# nixie_brain_main_rev7_1.net
KiCad netlist of a schematic drawn in EAGLE
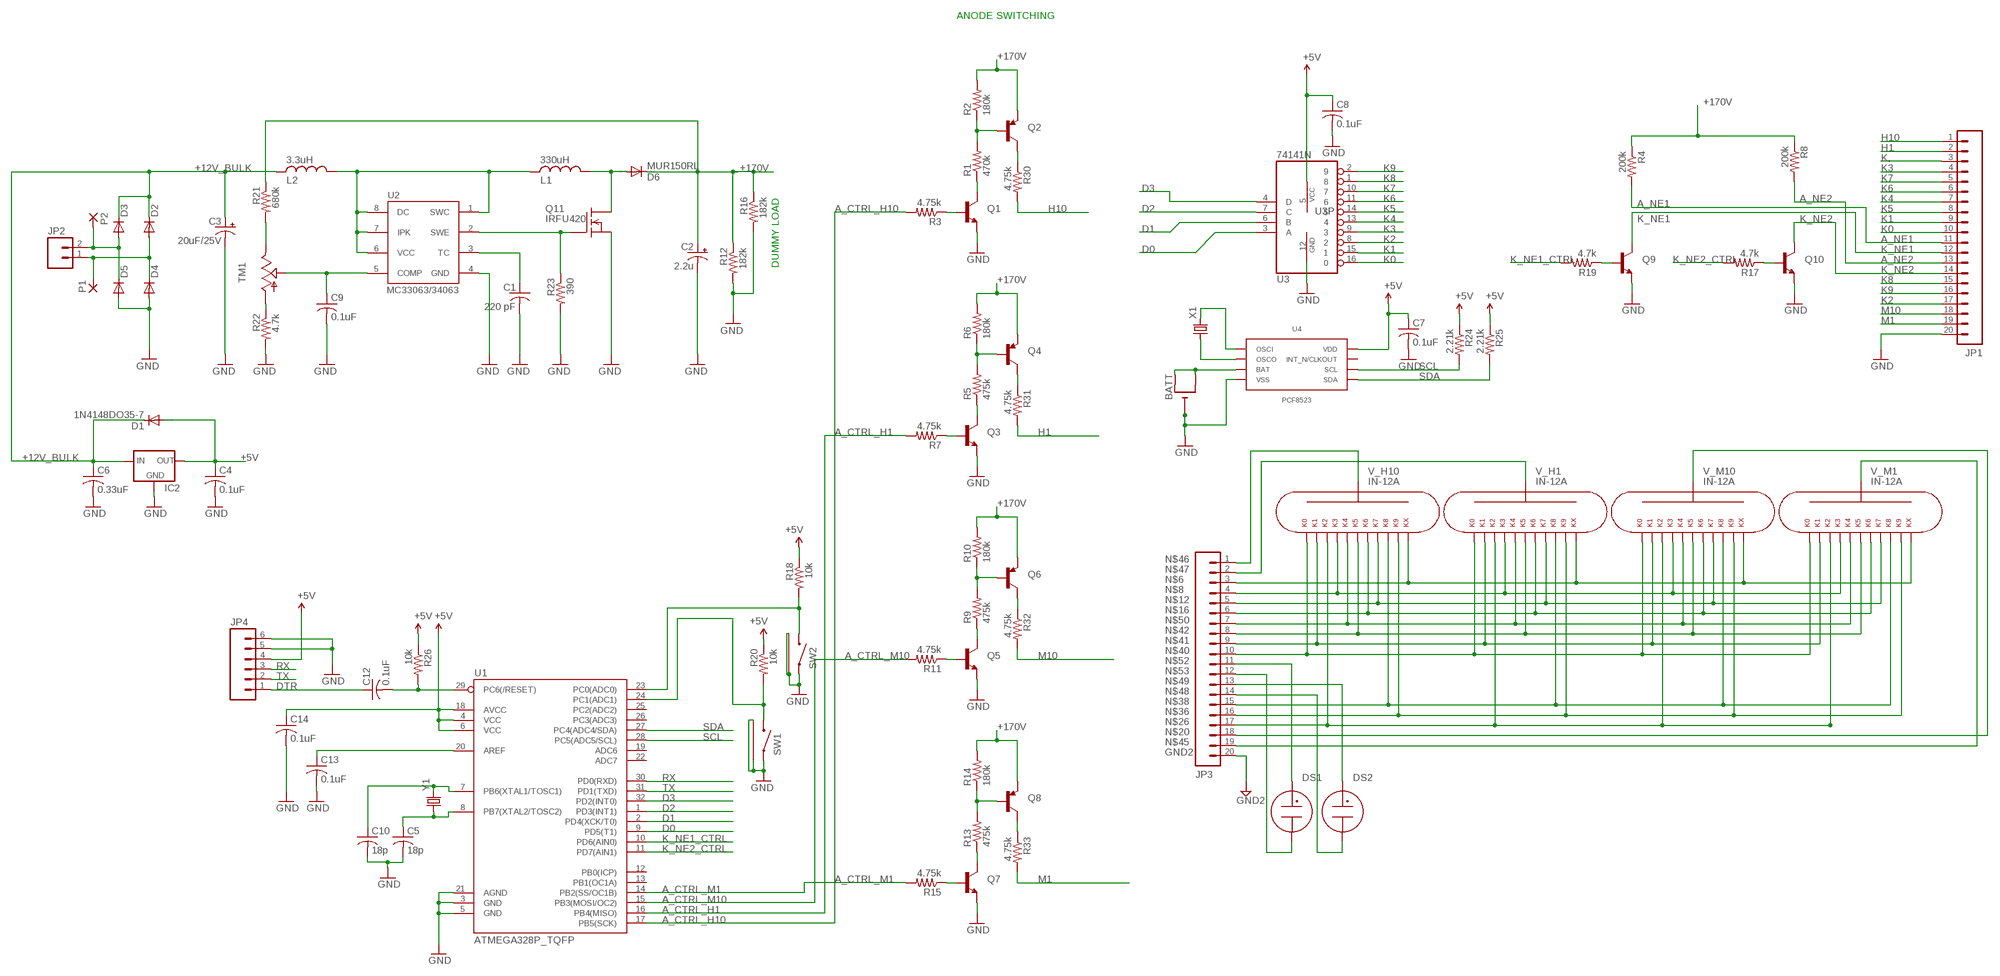
[diagram p0: schematic, sheet 1]

(export (version "E")
  (design (tool "Eeschema 10.0.6"))
  (components
    (comp (ref "BATT")
      (value "CR1220SMT")
      (footprint "eagle-import:CR1220-SMD")
      (libsource (lib "eagle-import") (part "CR1220SMT"))
    )
    (comp (ref "C1")
      (value "220 pF")
      (footprint "eagle-import:C025-025X050")
      (libsource (lib "eagle-import") (part "C-US025-025X050"))
    )
    (comp (ref "C2")
      (value "2.2u")
      (footprint "eagle-import:E5-8,5")
      (libsource (lib "eagle-import") (part "CPOL-USE5-8.5"))
    )
    (comp (ref "C3")
      (value "20uF/25V")
      (footprint "eagle-import:E2,5-5")
      (libsource (lib "eagle-import") (part "CPOL-USE2.5-5"))
    )
    (comp (ref "C4")
      (value "0.1uF")
      (footprint "eagle-import:C025-025X050")
      (libsource (lib "eagle-import") (part "C-US025-025X050"))
    )
    (comp (ref "C5")
      (value "18p")
      (footprint "eagle-import:C1206")
      (libsource (lib "eagle-import") (part "C-USC1206"))
    )
    (comp (ref "C6")
      (value "0.33uF")
      (footprint "eagle-import:C025-025X050")
      (libsource (lib "eagle-import") (part "C-US025-025X050"))
    )
    (comp (ref "C7")
      (value "0.1uF")
      (footprint "eagle-import:C025-025X050")
      (libsource (lib "eagle-import") (part "C-US025-025X050"))
    )
    (comp (ref "C8")
      (value "0.1uF")
      (footprint "eagle-import:C025-025X050")
      (libsource (lib "eagle-import") (part "C-US025-025X050"))
    )
    (comp (ref "C9")
      (value "0.1uF")
      (footprint "eagle-import:C025-025X050")
      (libsource (lib "eagle-import") (part "C-US025-025X050"))
    )
    (comp (ref "C10")
      (value "18p")
      (footprint "eagle-import:C1206")
      (libsource (lib "eagle-import") (part "C-USC1206"))
    )
    (comp (ref "C12")
      (value "0.1uF")
      (footprint "eagle-import:C025-025X050")
      (libsource (lib "eagle-import") (part "C-US025-025X050"))
    )
    (comp (ref "C13")
      (value "0.1uF")
      (footprint "eagle-import:C025-025X050")
      (libsource (lib "eagle-import") (part "C-US025-025X050"))
    )
    (comp (ref "C14")
      (value "0.1uF")
      (footprint "eagle-import:C025-025X050")
      (libsource (lib "eagle-import") (part "C-US025-025X050"))
    )
    (comp (ref "D1")
      (value "1N4148DO35-7")
      (footprint "eagle-import:DO35-7")
      (libsource (lib "eagle-import") (part "1N4148DO35-7"))
    )
    (comp (ref "D2")
      (value "DIODE1N4148")
      (footprint "eagle-import:DIODE-1N4148")
      (libsource (lib "eagle-import") (part "DIODE1N4148"))
    )
    (comp (ref "D3")
      (value "DIODE1N4148")
      (footprint "eagle-import:DIODE-1N4148")
      (libsource (lib "eagle-import") (part "DIODE1N4148"))
    )
    (comp (ref "D4")
      (value "DIODE1N4148")
      (footprint "eagle-import:DIODE-1N4148")
      (libsource (lib "eagle-import") (part "DIODE1N4148"))
    )
    (comp (ref "D5")
      (value "DIODE1N4148")
      (footprint "eagle-import:DIODE-1N4148")
      (libsource (lib "eagle-import") (part "DIODE1N4148"))
    )
    (comp (ref "D6")
      (value "MUR150RL")
      (footprint "eagle-import:DO41-10")
      (libsource (lib "eagle-import") (part "MUR150RL"))
    )
    (comp (ref "DS1")
      (value "NE-2")
      (footprint "eagle-import:NE-2")
      (libsource (lib "eagle-import") (part "NE-2"))
    )
    (comp (ref "DS2")
      (value "NE-2")
      (footprint "eagle-import:NE-2")
      (libsource (lib "eagle-import") (part "NE-2"))
    )
    (comp (ref "IC2")
      (value "V_REG_78XXSINK")
      (footprint "eagle-import:TO220-IGO")
      (libsource (lib "eagle-import") (part "V_REG_78XXSINK"))
    )
    (comp (ref "JP1")
      (value "M20LOCK")
      (footprint "eagle-import:1X20_LOCK")
      (libsource (lib "eagle-import") (part "M20LOCK"))
    )
    (comp (ref "JP2")
      (value "M02LOCK")
      (footprint "eagle-import:1X02_LOCK")
      (libsource (lib "eagle-import") (part "M02LOCK"))
    )
    (comp (ref "JP3")
      (value "M20LOCK")
      (footprint "eagle-import:1X20_LOCK")
      (libsource (lib "eagle-import") (part "M20LOCK"))
    )
    (comp (ref "JP4")
      (value "M06LOCK")
      (footprint "eagle-import:1X06_LOCK")
      (libsource (lib "eagle-import") (part "M06LOCK"))
    )
    (comp (ref "L1")
      (value "330uH")
      (footprint "eagle-import:22R334C")
      (libsource (lib "eagle-import") (part "22R334C"))
    )
    (comp (ref "L2")
      (value "3.3uH")
      (footprint "eagle-import:11R332C")
      (libsource (lib "eagle-import") (part "11R332C"))
    )
    (comp (ref "P1")
      (value "WIREPAD2,15/1,0")
      (footprint "eagle-import:2,15_1,0")
      (libsource (lib "eagle-import") (part "WIREPAD2,15/1,0"))
    )
    (comp (ref "P2")
      (value "WIREPAD2,15/1,0")
      (footprint "eagle-import:2,15_1,0")
      (libsource (lib "eagle-import") (part "WIREPAD2,15/1,0"))
    )
    (comp (ref "Q1")
      (value "MPSA42-NPN-TO92-EBC")
      (footprint "eagle-import:TO92-EBC")
      (libsource (lib "eagle-import") (part "-NPN-TO92-EBCMPSA42"))
    )
    (comp (ref "Q2")
      (value "MPSA92-PNP-TO92-EBC")
      (footprint "eagle-import:TO92-EBC")
      (libsource (lib "eagle-import") (part "-PNP-TO92-EBCMPSA92"))
    )
    (comp (ref "Q3")
      (value "MPSA42-NPN-TO92-EBC")
      (footprint "eagle-import:TO92-EBC")
      (libsource (lib "eagle-import") (part "-NPN-TO92-EBCMPSA42"))
    )
    (comp (ref "Q4")
      (value "MPSA92-PNP-TO92-EBC")
      (footprint "eagle-import:TO92-EBC")
      (libsource (lib "eagle-import") (part "-PNP-TO92-EBCMPSA92"))
    )
    (comp (ref "Q5")
      (value "MPSA42-NPN-TO92-EBC")
      (footprint "eagle-import:TO92-EBC")
      (libsource (lib "eagle-import") (part "-NPN-TO92-EBCMPSA42"))
    )
    (comp (ref "Q6")
      (value "MPSA92-PNP-TO92-EBC")
      (footprint "eagle-import:TO92-EBC")
      (libsource (lib "eagle-import") (part "-PNP-TO92-EBCMPSA92"))
    )
    (comp (ref "Q7")
      (value "MPSA42-NPN-TO92-EBC")
      (footprint "eagle-import:TO92-EBC")
      (libsource (lib "eagle-import") (part "-NPN-TO92-EBCMPSA42"))
    )
    (comp (ref "Q8")
      (value "MPSA92-PNP-TO92-EBC")
      (footprint "eagle-import:TO92-EBC")
      (libsource (lib "eagle-import") (part "-PNP-TO92-EBCMPSA92"))
    )
    (comp (ref "Q9")
      (value "MPSA42-NPN-TO92-EBC")
      (footprint "eagle-import:TO92-EBC")
      (libsource (lib "eagle-import") (part "-NPN-TO92-EBCMPSA42"))
    )
    (comp (ref "Q10")
      (value "MPSA42-NPN-TO92-EBC")
      (footprint "eagle-import:TO92-EBC")
      (libsource (lib "eagle-import") (part "-NPN-TO92-EBCMPSA42"))
    )
    (comp (ref "Q11")
      (value "IRFU420")
      (footprint "eagle-import:IRFU420")
      (libsource (lib "eagle-import") (part "IRFU420"))
    )
    (comp (ref "R1")
      (value "470k")
      (footprint "eagle-import:R1206")
      (libsource (lib "eagle-import") (part "R-US_R1206"))
    )
    (comp (ref "R2")
      (value "180k")
      (footprint "eagle-import:R1206")
      (libsource (lib "eagle-import") (part "R-US_R1206"))
    )
    (comp (ref "R3")
      (value "4.75k")
      (footprint "eagle-import:R1206")
      (libsource (lib "eagle-import") (part "R-US_R1206"))
    )
    (comp (ref "R4")
      (value "200k")
      (footprint "eagle-import:R1206")
      (libsource (lib "eagle-import") (part "R-US_R1206"))
    )
    (comp (ref "R5")
      (value "475k")
      (footprint "eagle-import:R1206")
      (libsource (lib "eagle-import") (part "R-US_R1206"))
    )
    (comp (ref "R6")
      (value "180k")
      (footprint "eagle-import:R1206")
      (libsource (lib "eagle-import") (part "R-US_R1206"))
    )
    (comp (ref "R7")
      (value "4.75k")
      (footprint "eagle-import:R1206")
      (libsource (lib "eagle-import") (part "R-US_R1206"))
    )
    (comp (ref "R8")
      (value "200k")
      (footprint "eagle-import:R1206")
      (libsource (lib "eagle-import") (part "R-US_R1206"))
    )
    (comp (ref "R9")
      (value "475k")
      (footprint "eagle-import:R1206")
      (libsource (lib "eagle-import") (part "R-US_R1206"))
    )
    (comp (ref "R10")
      (value "180k")
      (footprint "eagle-import:R1206")
      (libsource (lib "eagle-import") (part "R-US_R1206"))
    )
    (comp (ref "R11")
      (value "4.75k")
      (footprint "eagle-import:R1206")
      (libsource (lib "eagle-import") (part "R-US_R1206"))
    )
    (comp (ref "R12")
      (value "182k")
      (footprint "eagle-import:R1206")
      (libsource (lib "eagle-import") (part "R-US_R1206"))
    )
    (comp (ref "R13")
      (value "475k")
      (footprint "eagle-import:R1206")
      (libsource (lib "eagle-import") (part "R-US_R1206"))
    )
    (comp (ref "R14")
      (value "180k")
      (footprint "eagle-import:R1206")
      (libsource (lib "eagle-import") (part "R-US_R1206"))
    )
    (comp (ref "R15")
      (value "4.75k")
      (footprint "eagle-import:R1206")
      (libsource (lib "eagle-import") (part "R-US_R1206"))
    )
    (comp (ref "R16")
      (value "182k")
      (footprint "eagle-import:R1206")
      (libsource (lib "eagle-import") (part "R-US_R1206"))
    )
    (comp (ref "R17")
      (value "4.7k")
      (footprint "eagle-import:R1206")
      (libsource (lib "eagle-import") (part "R-US_R1206"))
    )
    (comp (ref "R18")
      (value "10k")
      (footprint "eagle-import:R1206")
      (libsource (lib "eagle-import") (part "R-US_R1206"))
    )
    (comp (ref "R19")
      (value "4.7k")
      (footprint "eagle-import:R1206")
      (libsource (lib "eagle-import") (part "R-US_R1206"))
    )
    (comp (ref "R20")
      (value "10k")
      (footprint "eagle-import:R1206")
      (libsource (lib "eagle-import") (part "R-US_R1206"))
    )
    (comp (ref "R21")
      (value "680k")
      (footprint "eagle-import:R1206")
      (libsource (lib "eagle-import") (part "R-US_R1206"))
    )
    (comp (ref "R22")
      (value "4.7k")
      (footprint "eagle-import:R1206")
      (libsource (lib "eagle-import") (part "R-US_R1206"))
    )
    (comp (ref "R23")
      (value "390")
      (footprint "eagle-import:R1206")
      (libsource (lib "eagle-import") (part "R-US_R1206"))
    )
    (comp (ref "R24")
      (value "2.21k")
      (footprint "eagle-import:R1206")
      (libsource (lib "eagle-import") (part "R-US_R1206"))
    )
    (comp (ref "R25")
      (value "2.21k")
      (footprint "eagle-import:R1206")
      (libsource (lib "eagle-import") (part "R-US_R1206"))
    )
    (comp (ref "R26")
      (value "10k")
      (footprint "eagle-import:R1206")
      (libsource (lib "eagle-import") (part "R-US_R1206"))
    )
    (comp (ref "R30")
      (value "4.75k")
      (footprint "eagle-import:R1206")
      (libsource (lib "eagle-import") (part "R-US_R1206"))
    )
    (comp (ref "R31")
      (value "4.75k")
      (footprint "eagle-import:R1206")
      (libsource (lib "eagle-import") (part "R-US_R1206"))
    )
    (comp (ref "R32")
      (value "4.75k")
      (footprint "eagle-import:R1206")
      (libsource (lib "eagle-import") (part "R-US_R1206"))
    )
    (comp (ref "R33")
      (value "4.75k")
      (footprint "eagle-import:R1206")
      (libsource (lib "eagle-import") (part "R-US_R1206"))
    )
    (comp (ref "SW1")
      (value "CT1102V5-85F100")
      (footprint "eagle-import:CT1102V5-85F100")
      (libsource (lib "eagle-import") (part "CT1102V5-85F100"))
    )
    (comp (ref "SW2")
      (value "CT1102V5-85F100")
      (footprint "eagle-import:CT1102V5-85F100")
      (libsource (lib "eagle-import") (part "CT1102V5-85F100"))
    )
    (comp (ref "TM1")
      (value "TRIM")
      (footprint "eagle-import:6MM")
      (libsource (lib "eagle-import") (part "TRIM"))
    )
    (comp (ref "U1")
      (value "ATMEGA328P_TQFP")
      (footprint "eagle-import:TQFP32-08")
      (libsource (lib "eagle-import") (part "ATMEGA328P_TQFP"))
    )
    (comp (ref "U2")
      (value "MC33063/MC34063P")
      (footprint "eagle-import:DIL08")
      (libsource (lib "eagle-import") (part "MC33063/MC34063P"))
    )
    (comp (ref "U3")
      (value "74141N")
      (footprint "eagle-import:DIL16")
      (libsource (lib "eagle-import") (part "74141N"))
    )
    (comp (ref "U4")
      (value "PCF8523")
      (footprint "eagle-import:PCF8523")
      (libsource (lib "eagle-import") (part "PCF8523"))
    )
    (comp (ref "V_H1")
      (value "IN-12A")
      (footprint "eagle-import:IN-12A")
      (libsource (lib "eagle-import") (part "IN-12A"))
    )
    (comp (ref "V_H10")
      (value "IN-12A")
      (footprint "eagle-import:IN-12A")
      (libsource (lib "eagle-import") (part "IN-12A"))
    )
    (comp (ref "V_M1")
      (value "IN-12A")
      (footprint "eagle-import:IN-12A")
      (libsource (lib "eagle-import") (part "IN-12A"))
    )
    (comp (ref "V_M10")
      (value "IN-12A")
      (footprint "eagle-import:IN-12A")
      (libsource (lib "eagle-import") (part "IN-12A"))
    )
    (comp (ref "X1")
      (value "MC-306")
      (footprint "eagle-import:MC-306")
      (fields (field (name "MPN") "MC-306 60.0KHZ  100PPM ,12.5PF"))
      (libsource (lib "eagle-import") (part "MC-306"))
    )
    (comp (ref "Y1")
      (value "CRYSTAL5X3")
      (footprint "eagle-import:CRYSTAL-SMD-5X3")
      (libsource (lib "eagle-import") (part "CRYSTAL5X3"))
    )
  )
  (nets
    (net (code "1") (name "+5V") (class "Default")
      (node (ref "C14") (pin "1") (pinfunction "1_1") (pintype "passive"))
      (node (ref "C4") (pin "1") (pinfunction "1_1") (pintype "passive"))
      (node (ref "C7") (pin "1") (pinfunction "1_1") (pintype "passive"))
      (node (ref "C8") (pin "1") (pinfunction "1_1") (pintype "passive"))
      (node (ref "D1") (pin "A") (pinfunction "A_A") (pintype "passive"))
      (node (ref "IC2") (pin "OUT") (pinfunction "OUT_OUT") (pintype "output"))
      (node (ref "JP4") (pin "4") (pinfunction "4_4") (pintype "passive"))
      (node (ref "R18") (pin "1") (pinfunction "1_1") (pintype "passive"))
      (node (ref "R20") (pin "1") (pinfunction "1_1") (pintype "passive"))
      (node (ref "R24") (pin "1") (pinfunction "1_1") (pintype "passive"))
      (node (ref "R25") (pin "1") (pinfunction "1_1") (pintype "passive"))
      (node (ref "R26") (pin "1") (pinfunction "1_1") (pintype "passive"))
      (node (ref "U1") (pin "18") (pinfunction "AVCC_18") (pintype "bidirectional"))
      (node (ref "U1") (pin "4") (pinfunction "VCC_4") (pintype "bidirectional"))
      (node (ref "U1") (pin "6") (pinfunction "VCC_6") (pintype "bidirectional"))
      (node (ref "U3") (pin "5") (pinfunction "VCC_5") (pintype "power_in"))
      (node (ref "U4") (pin "8") (pinfunction "P8_VDD_8") (pintype "power_in"))
    )
    (net (code "2") (name "/+12V_BULK") (class "Default")
      (node (ref "C3") (pin "+") (pinfunction "+_+") (pintype "passive"))
      (node (ref "C6") (pin "1") (pinfunction "1_1") (pintype "passive"))
      (node (ref "D1") (pin "C") (pinfunction "C_C") (pintype "passive"))
      (node (ref "D2") (pin "C") (pinfunction "C_C") (pintype "passive"))
      (node (ref "D3") (pin "C") (pinfunction "C_C") (pintype "passive"))
      (node (ref "IC2") (pin "IN") (pinfunction "IN_IN") (pintype "input"))
      (node (ref "L2") (pin "P$2") (pinfunction "2_P$2") (pintype "passive"))
    )
    (net (code "3") (name "/+170V") (class "Default")
      (node (ref "C2") (pin "+") (pinfunction "+_+") (pintype "passive"))
      (node (ref "D6") (pin "C") (pinfunction "C_C") (pintype "passive"))
      (node (ref "Q2") (pin "E") (pinfunction "E_E") (pintype "passive"))
      (node (ref "Q4") (pin "E") (pinfunction "E_E") (pintype "passive"))
      (node (ref "Q6") (pin "E") (pinfunction "E_E") (pintype "passive"))
      (node (ref "Q8") (pin "E") (pinfunction "E_E") (pintype "passive"))
      (node (ref "R10") (pin "2") (pinfunction "2_2") (pintype "passive"))
      (node (ref "R12") (pin "1") (pinfunction "1_1") (pintype "passive"))
      (node (ref "R14") (pin "2") (pinfunction "2_2") (pintype "passive"))
      (node (ref "R16") (pin "1") (pinfunction "1_1") (pintype "passive"))
      (node (ref "R2") (pin "2") (pinfunction "2_2") (pintype "passive"))
      (node (ref "R21") (pin "1") (pinfunction "1_1") (pintype "passive"))
      (node (ref "R4") (pin "1") (pinfunction "1_1") (pintype "passive"))
      (node (ref "R6") (pin "2") (pinfunction "2_2") (pintype "passive"))
      (node (ref "R8") (pin "1") (pinfunction "1_1") (pintype "passive"))
    )
    (net (code "4") (name "/A_CTRL_H1") (class "Default")
      (node (ref "R7") (pin "2") (pinfunction "2_2") (pintype "passive"))
      (node (ref "U1") (pin "16") (pinfunction "PB4(MISO)_16") (pintype "bidirectional"))
    )
    (net (code "5") (name "/A_CTRL_H10") (class "Default")
      (node (ref "R3") (pin "2") (pinfunction "2_2") (pintype "passive"))
      (node (ref "U1") (pin "17") (pinfunction "PB5(SCK)_17") (pintype "bidirectional"))
    )
    (net (code "6") (name "/A_CTRL_M1") (class "Default")
      (node (ref "R15") (pin "2") (pinfunction "2_2") (pintype "passive"))
      (node (ref "U1") (pin "14") (pinfunction "PB2(SS/OC1B)_14") (pintype "bidirectional"))
    )
    (net (code "7") (name "/A_CTRL_M10") (class "Default")
      (node (ref "R11") (pin "2") (pinfunction "2_2") (pintype "passive"))
      (node (ref "U1") (pin "15") (pinfunction "PB3(MOSI/OC2)_15") (pintype "bidirectional"))
    )
    (net (code "8") (name "/A_NE1") (class "Default")
      (node (ref "JP1") (pin "11") (pinfunction "11_11") (pintype "passive"))
      (node (ref "R4") (pin "2") (pinfunction "2_2") (pintype "passive"))
    )
    (net (code "9") (name "/A_NE2") (class "Default")
      (node (ref "JP1") (pin "13") (pinfunction "13_13") (pintype "passive"))
      (node (ref "R8") (pin "2") (pinfunction "2_2") (pintype "passive"))
    )
    (net (code "10") (name "/D0") (class "Default")
      (node (ref "U1") (pin "9") (pinfunction "PD5(T1)_9") (pintype "bidirectional"))
      (node (ref "U3") (pin "3") (pinfunction "A_3") (pintype "input"))
    )
    (net (code "11") (name "/D1") (class "Default")
      (node (ref "U1") (pin "2") (pinfunction "PD4(XCK/T0)_2") (pintype "bidirectional"))
      (node (ref "U3") (pin "6") (pinfunction "B_6") (pintype "input"))
    )
    (net (code "12") (name "/D2") (class "Default")
      (node (ref "U1") (pin "1") (pinfunction "PD3(INT1)_1") (pintype "bidirectional"))
      (node (ref "U3") (pin "7") (pinfunction "C_7") (pintype "input"))
    )
    (net (code "13") (name "/D3") (class "Default")
      (node (ref "U1") (pin "32") (pinfunction "PD2(INT0)_32") (pintype "bidirectional"))
      (node (ref "U3") (pin "4") (pinfunction "D_4") (pintype "input"))
    )
    (net (code "14") (name "/DTR") (class "Default")
      (node (ref "C12") (pin "1") (pinfunction "1_1") (pintype "passive"))
      (node (ref "JP4") (pin "1") (pinfunction "1_1") (pintype "passive"))
    )
    (net (code "15") (name "/H1") (class "Default")
      (node (ref "JP1") (pin "2") (pinfunction "2_2") (pintype "passive"))
      (node (ref "R31") (pin "2") (pinfunction "2_2") (pintype "passive"))
    )
    (net (code "16") (name "/H10") (class "Default")
      (node (ref "JP1") (pin "1") (pinfunction "1_1") (pintype "passive"))
      (node (ref "R30") (pin "2") (pinfunction "2_2") (pintype "passive"))
    )
    (net (code "17") (name "/K,") (class "Default")
      (node (ref "JP1") (pin "3") (pinfunction "3_3") (pintype "passive"))
    )
    (net (code "18") (name "/K0") (class "Default")
      (node (ref "JP1") (pin "10") (pinfunction "10_10") (pintype "passive"))
      (node (ref "U3") (pin "16") (pinfunction "0_16") (pintype "open_collector"))
    )
    (net (code "19") (name "/K1") (class "Default")
      (node (ref "JP1") (pin "9") (pinfunction "9_9") (pintype "passive"))
      (node (ref "U3") (pin "15") (pinfunction "1_15") (pintype "open_collector"))
    )
    (net (code "20") (name "/K2") (class "Default")
      (node (ref "JP1") (pin "17") (pinfunction "17_17") (pintype "passive"))
      (node (ref "U3") (pin "8") (pinfunction "2_8") (pintype "open_collector"))
    )
    (net (code "21") (name "/K3") (class "Default")
      (node (ref "JP1") (pin "4") (pinfunction "4_4") (pintype "passive"))
      (node (ref "U3") (pin "9") (pinfunction "3_9") (pintype "open_collector"))
    )
    (net (code "22") (name "/K4") (class "Default")
      (node (ref "JP1") (pin "7") (pinfunction "7_7") (pintype "passive"))
      (node (ref "U3") (pin "13") (pinfunction "4_13") (pintype "open_collector"))
    )
    (net (code "23") (name "/K5") (class "Default")
      (node (ref "JP1") (pin "8") (pinfunction "8_8") (pintype "passive"))
      (node (ref "U3") (pin "14") (pinfunction "5_14") (pintype "open_collector"))
    )
    (net (code "24") (name "/K6") (class "Default")
      (node (ref "JP1") (pin "6") (pinfunction "6_6") (pintype "passive"))
      (node (ref "U3") (pin "11") (pinfunction "6_11") (pintype "open_collector"))
    )
    (net (code "25") (name "/K7") (class "Default")
      (node (ref "JP1") (pin "5") (pinfunction "5_5") (pintype "passive"))
      (node (ref "U3") (pin "10") (pinfunction "7_10") (pintype "open_collector"))
    )
    (net (code "26") (name "/K8") (class "Default")
      (node (ref "JP1") (pin "15") (pinfunction "15_15") (pintype "passive"))
      (node (ref "U3") (pin "1") (pinfunction "8_1") (pintype "open_collector"))
    )
    (net (code "27") (name "/K9") (class "Default")
      (node (ref "JP1") (pin "16") (pinfunction "16_16") (pintype "passive"))
      (node (ref "U3") (pin "2") (pinfunction "9_2") (pintype "open_collector"))
    )
    (net (code "28") (name "/K_NE1") (class "Default")
      (node (ref "JP1") (pin "12") (pinfunction "12_12") (pintype "passive"))
      (node (ref "Q9") (pin "C") (pinfunction "C_C") (pintype "passive"))
    )
    (net (code "29") (name "/K_NE1_CTRL") (class "Default")
      (node (ref "R19") (pin "2") (pinfunction "2_2") (pintype "passive"))
      (node (ref "U1") (pin "10") (pinfunction "PD6(AIN0)_10") (pintype "bidirectional"))
    )
    (net (code "30") (name "/K_NE2") (class "Default")
      (node (ref "JP1") (pin "14") (pinfunction "14_14") (pintype "passive"))
      (node (ref "Q10") (pin "C") (pinfunction "C_C") (pintype "passive"))
    )
    (net (code "31") (name "/K_NE2_CTRL") (class "Default")
      (node (ref "R17") (pin "2") (pinfunction "2_2") (pintype "passive"))
      (node (ref "U1") (pin "11") (pinfunction "PD7(AIN1)_11") (pintype "bidirectional"))
    )
    (net (code "32") (name "/M1") (class "Default")
      (node (ref "JP1") (pin "19") (pinfunction "19_19") (pintype "passive"))
      (node (ref "R33") (pin "2") (pinfunction "2_2") (pintype "passive"))
    )
    (net (code "33") (name "/M10") (class "Default")
      (node (ref "JP1") (pin "18") (pinfunction "18_18") (pintype "passive"))
      (node (ref "R32") (pin "2") (pinfunction "2_2") (pintype "passive"))
    )
    (net (code "34") (name "/N$6") (class "Default")
      (node (ref "JP3") (pin "3") (pinfunction "3_3") (pintype "passive"))
      (node (ref "V_H1") (pin "P12_KX") (pinfunction "NC_P12_KX") (pintype "bidirectional"))
      (node (ref "V_H10") (pin "P12_KX") (pinfunction "NC_P12_KX") (pintype "bidirectional"))
      (node (ref "V_M1") (pin "P12_KX") (pinfunction "NC_P12_KX") (pintype "bidirectional"))
      (node (ref "V_M10") (pin "P12_KX") (pinfunction "NC_P12_KX") (pintype "bidirectional"))
    )
    (net (code "35") (name "/N$8") (class "Default")
      (node (ref "JP3") (pin "4") (pinfunction "4_4") (pintype "passive"))
      (node (ref "V_H1") (pin "P9_K3") (pinfunction "K3_P9_K3") (pintype "bidirectional"))
      (node (ref "V_H10") (pin "P9_K3") (pinfunction "K3_P9_K3") (pintype "bidirectional"))
      (node (ref "V_M1") (pin "P9_K3") (pinfunction "K3_P9_K3") (pintype "bidirectional"))
      (node (ref "V_M10") (pin "P9_K3") (pinfunction "K3_P9_K3") (pintype "bidirectional"))
    )
    (net (code "36") (name "/N$12") (class "Default")
      (node (ref "JP3") (pin "5") (pinfunction "5_5") (pintype "passive"))
      (node (ref "V_H1") (pin "P5_K7") (pinfunction "K7_P5_K7") (pintype "bidirectional"))
      (node (ref "V_H10") (pin "P5_K7") (pinfunction "K7_P5_K7") (pintype "bidirectional"))
      (node (ref "V_M1") (pin "P5_K7") (pinfunction "K7_P5_K7") (pintype "bidirectional"))
      (node (ref "V_M10") (pin "P5_K7") (pinfunction "K7_P5_K7") (pintype "bidirectional"))
    )
    (net (code "37") (name "/N$16") (class "Default")
      (node (ref "JP3") (pin "6") (pinfunction "6_6") (pintype "passive"))
      (node (ref "V_H1") (pin "P6_K6") (pinfunction "K6_P6_K6") (pintype "bidirectional"))
      (node (ref "V_H10") (pin "P6_K6") (pinfunction "K6_P6_K6") (pintype "bidirectional"))
      (node (ref "V_M1") (pin "P6_K6") (pinfunction "K6_P6_K6") (pintype "bidirectional"))
      (node (ref "V_M10") (pin "P6_K6") (pinfunction "K6_P6_K6") (pintype "bidirectional"))
    )
    (net (code "38") (name "/N$20") (class "Default")
      (node (ref "JP3") (pin "18") (pinfunction "18_18") (pintype "passive"))
      (node (ref "V_M10") (pin "P1_A") (pinfunction "A_P1_A") (pintype "bidirectional"))
    )
    (net (code "39") (name "/N$26") (class "Default")
      (node (ref "JP3") (pin "17") (pinfunction "17_17") (pintype "passive"))
      (node (ref "V_H1") (pin "P10_K2") (pinfunction "K2_P10_K2") (pintype "bidirectional"))
      (node (ref "V_H10") (pin "P10_K2") (pinfunction "K2_P10_K2") (pintype "bidirectional"))
      (node (ref "V_M1") (pin "P10_K2") (pinfunction "K2_P10_K2") (pintype "bidirectional"))
      (node (ref "V_M10") (pin "P10_K2") (pinfunction "K2_P10_K2") (pintype "bidirectional"))
    )
    (net (code "40") (name "/N$36") (class "Default")
      (node (ref "JP3") (pin "16") (pinfunction "16_16") (pintype "passive"))
      (node (ref "V_H1") (pin "P3_K9") (pinfunction "K9_P3_K9") (pintype "bidirectional"))
      (node (ref "V_H10") (pin "P3_K9") (pinfunction "K9_P3_K9") (pintype "bidirectional"))
      (node (ref "V_M1") (pin "P3_K9") (pinfunction "K9_P3_K9") (pintype "bidirectional"))
      (node (ref "V_M10") (pin "P3_K9") (pinfunction "K9_P3_K9") (pintype "bidirectional"))
    )
    (net (code "41") (name "/N$38") (class "Default")
      (node (ref "JP3") (pin "15") (pinfunction "15_15") (pintype "passive"))
      (node (ref "V_H1") (pin "P4_K8") (pinfunction "K8_P4_K8") (pintype "bidirectional"))
      (node (ref "V_H10") (pin "P4_K8") (pinfunction "K8_P4_K8") (pintype "bidirectional"))
      (node (ref "V_M1") (pin "P4_K8") (pinfunction "K8_P4_K8") (pintype "bidirectional"))
      (node (ref "V_M10") (pin "P4_K8") (pinfunction "K8_P4_K8") (pintype "bidirectional"))
    )
    (net (code "42") (name "/N$40") (class "Default")
      (node (ref "JP3") (pin "10") (pinfunction "10_10") (pintype "passive"))
      (node (ref "V_H1") (pin "P2_K0") (pinfunction "K0_P2_K0") (pintype "bidirectional"))
      (node (ref "V_H10") (pin "P2_K0") (pinfunction "K0_P2_K0") (pintype "bidirectional"))
      (node (ref "V_M1") (pin "P2_K0") (pinfunction "K0_P2_K0") (pintype "bidirectional"))
      (node (ref "V_M10") (pin "P2_K0") (pinfunction "K0_P2_K0") (pintype "bidirectional"))
    )
    (net (code "43") (name "/N$41") (class "Default")
      (node (ref "JP3") (pin "9") (pinfunction "9_9") (pintype "passive"))
      (node (ref "V_H1") (pin "P11_K1") (pinfunction "K1_P11_K1") (pintype "bidirectional"))
      (node (ref "V_H10") (pin "P11_K1") (pinfunction "K1_P11_K1") (pintype "bidirectional"))
      (node (ref "V_M1") (pin "P11_K1") (pinfunction "K1_P11_K1") (pintype "bidirectional"))
      (node (ref "V_M10") (pin "P11_K1") (pinfunction "K1_P11_K1") (pintype "bidirectional"))
    )
    (net (code "44") (name "/N$42") (class "Default")
      (node (ref "JP3") (pin "8") (pinfunction "8_8") (pintype "passive"))
      (node (ref "V_H1") (pin "P7_K5") (pinfunction "K5_P7_K5") (pintype "bidirectional"))
      (node (ref "V_H10") (pin "P7_K5") (pinfunction "K5_P7_K5") (pintype "bidirectional"))
      (node (ref "V_M1") (pin "P7_K5") (pinfunction "K5_P7_K5") (pintype "bidirectional"))
      (node (ref "V_M10") (pin "P7_K5") (pinfunction "K5_P7_K5") (pintype "bidirectional"))
    )
    (net (code "45") (name "/N$45") (class "Default")
      (node (ref "JP3") (pin "19") (pinfunction "19_19") (pintype "passive"))
      (node (ref "V_M1") (pin "P1_A") (pinfunction "A_P1_A") (pintype "bidirectional"))
    )
    (net (code "46") (name "/N$46") (class "Default")
      (node (ref "JP3") (pin "1") (pinfunction "1_1") (pintype "passive"))
      (node (ref "V_H10") (pin "P1_A") (pinfunction "A_P1_A") (pintype "bidirectional"))
    )
    (net (code "47") (name "/N$47") (class "Default")
      (node (ref "JP3") (pin "2") (pinfunction "2_2") (pintype "passive"))
      (node (ref "V_H1") (pin "P1_A") (pinfunction "A_P1_A") (pintype "bidirectional"))
    )
    (net (code "48") (name "/N$48") (class "Default")
      (node (ref "DS2") (pin "K") (pinfunction "K_K") (pintype "bidirectional"))
      (node (ref "JP3") (pin "14") (pinfunction "14_14") (pintype "passive"))
    )
    (net (code "49") (name "/N$49") (class "Default")
      (node (ref "DS2") (pin "A") (pinfunction "A_A") (pintype "bidirectional"))
      (node (ref "JP3") (pin "13") (pinfunction "13_13") (pintype "passive"))
    )
    (net (code "50") (name "/N$50") (class "Default")
      (node (ref "JP3") (pin "7") (pinfunction "7_7") (pintype "passive"))
      (node (ref "V_H1") (pin "P8_K4") (pinfunction "K4_P8_K4") (pintype "bidirectional"))
      (node (ref "V_H10") (pin "P8_K4") (pinfunction "K4_P8_K4") (pintype "bidirectional"))
      (node (ref "V_M1") (pin "P8_K4") (pinfunction "K4_P8_K4") (pintype "bidirectional"))
      (node (ref "V_M10") (pin "P8_K4") (pinfunction "K4_P8_K4") (pintype "bidirectional"))
    )
    (net (code "51") (name "/N$52") (class "Default")
      (node (ref "DS1") (pin "A") (pinfunction "A_A") (pintype "bidirectional"))
      (node (ref "JP3") (pin "11") (pinfunction "11_11") (pintype "passive"))
    )
    (net (code "52") (name "/N$53") (class "Default")
      (node (ref "DS1") (pin "K") (pinfunction "K_K") (pintype "bidirectional"))
      (node (ref "JP3") (pin "12") (pinfunction "12_12") (pintype "passive"))
    )
    (net (code "53") (name "/RX") (class "Default")
      (node (ref "JP4") (pin "3") (pinfunction "3_3") (pintype "passive"))
      (node (ref "U1") (pin "30") (pinfunction "PD0(RXD)_30") (pintype "bidirectional"))
    )
    (net (code "54") (name "/SCL") (class "Default")
      (node (ref "R24") (pin "2") (pinfunction "2_2") (pintype "passive"))
      (node (ref "U1") (pin "28") (pinfunction "PC5(ADC5/SCL)_28") (pintype "bidirectional"))
      (node (ref "U4") (pin "6") (pinfunction "P6_SCL_6") (pintype "bidirectional"))
    )
    (net (code "55") (name "/SDA") (class "Default")
      (node (ref "R25") (pin "2") (pinfunction "2_2") (pintype "passive"))
      (node (ref "U1") (pin "27") (pinfunction "PC4(ADC4/SDA)_27") (pintype "bidirectional"))
      (node (ref "U4") (pin "5") (pinfunction "P5_SDA_5") (pintype "bidirectional"))
    )
    (net (code "56") (name "/TX") (class "Default")
      (node (ref "JP4") (pin "2") (pinfunction "2_2") (pintype "passive"))
      (node (ref "U1") (pin "31") (pinfunction "PD1(TXD)_31") (pintype "bidirectional"))
    )
    (net (code "57") (name "GND") (class "Default")
      (node (ref "BATT") (pin "-") (pinfunction "-_-") (pintype "passive"))
      (node (ref "C1") (pin "2") (pinfunction "2_2") (pintype "passive"))
      (node (ref "C10") (pin "2") (pinfunction "2_2") (pintype "passive"))
      (node (ref "C13") (pin "2") (pinfunction "2_2") (pintype "passive"))
      (node (ref "C14") (pin "2") (pinfunction "2_2") (pintype "passive"))
      (node (ref "C2") (pin "-") (pinfunction "-_-") (pintype "passive"))
      (node (ref "C3") (pin "-") (pinfunction "-_-") (pintype "passive"))
      (node (ref "C4") (pin "2") (pinfunction "2_2") (pintype "passive"))
      (node (ref "C5") (pin "2") (pinfunction "2_2") (pintype "passive"))
      (node (ref "C6") (pin "2") (pinfunction "2_2") (pintype "passive"))
      (node (ref "C7") (pin "2") (pinfunction "2_2") (pintype "passive"))
      (node (ref "C8") (pin "2") (pinfunction "2_2") (pintype "passive"))
      (node (ref "C9") (pin "2") (pinfunction "2_2") (pintype "passive"))
      (node (ref "D4") (pin "A") (pinfunction "A_A") (pintype "passive"))
      (node (ref "D5") (pin "A") (pinfunction "A_A") (pintype "passive"))
      (node (ref "IC2") (pin "GND") (pinfunction "GND_GND") (pintype "input"))
      (node (ref "JP1") (pin "20") (pinfunction "20_20") (pintype "passive"))
      (node (ref "JP4") (pin "5") (pinfunction "5_5") (pintype "passive"))
      (node (ref "JP4") (pin "6") (pinfunction "6_6") (pintype "passive"))
      (node (ref "Q1") (pin "E") (pinfunction "E_E") (pintype "passive"))
      (node (ref "Q10") (pin "E") (pinfunction "E_E") (pintype "passive"))
      (node (ref "Q11") (pin "S") (pinfunction "S_S") (pintype "passive"))
      (node (ref "Q3") (pin "E") (pinfunction "E_E") (pintype "passive"))
      (node (ref "Q5") (pin "E") (pinfunction "E_E") (pintype "passive"))
      (node (ref "Q7") (pin "E") (pinfunction "E_E") (pintype "passive"))
      (node (ref "Q9") (pin "E") (pinfunction "E_E") (pintype "passive"))
      (node (ref "R12") (pin "2") (pinfunction "2_2") (pintype "passive"))
      (node (ref "R16") (pin "2") (pinfunction "2_2") (pintype "passive"))
      (node (ref "R22") (pin "2") (pinfunction "2_2") (pintype "passive"))
      (node (ref "R23") (pin "2") (pinfunction "2_2") (pintype "passive"))
      (node (ref "SW1") (pin "P$3") (pinfunction "P3_CHASSIS_P$3") (pintype "bidirectional"))
      (node (ref "SW1") (pin "P$4") (pinfunction "P4_CHASSIS_P$4") (pintype "bidirectional"))
      (node (ref "SW1") (pin "P1_SW") (pinfunction "P1_SW_P1_SW") (pintype "bidirectional"))
      (node (ref "SW2") (pin "P$3") (pinfunction "P3_CHASSIS_P$3") (pintype "bidirectional"))
      (node (ref "SW2") (pin "P$4") (pinfunction "P4_CHASSIS_P$4") (pintype "bidirectional"))
      (node (ref "SW2") (pin "P1_SW") (pinfunction "P1_SW_P1_SW") (pintype "bidirectional"))
      (node (ref "U1") (pin "21") (pinfunction "AGND_21") (pintype "bidirectional"))
      (node (ref "U1") (pin "3") (pinfunction "GND_3") (pintype "bidirectional"))
      (node (ref "U1") (pin "5") (pinfunction "GND_5") (pintype "bidirectional"))
      (node (ref "U2") (pin "4") (pinfunction "GND_4") (pintype "power_in"))
      (node (ref "U3") (pin "12") (pinfunction "GND_12") (pintype "power_in"))
      (node (ref "U4") (pin "4") (pinfunction "P4_VSS_4") (pintype "power_in"))
    )
    (net (code "58") (name "GND2") (class "Default")
      (node (ref "JP3") (pin "20") (pinfunction "20_20") (pintype "passive"))
    )
    (net (code "59") (name "Net-(BATT-+)") (class "Default")
      (node (ref "BATT") (pin "+$1") (pinfunction "+_+$1") (pintype "passive"))
      (node (ref "BATT") (pin "+$2") (pinfunction "+1_+$2") (pintype "passive"))
      (node (ref "U4") (pin "3") (pinfunction "P3_BAT_3") (pintype "power_in"))
    )
    (net (code "60") (name "Net-(L1-1)") (class "Default")
      (node (ref "D6") (pin "A") (pinfunction "A_A") (pintype "passive"))
      (node (ref "L1") (pin "P$1") (pinfunction "1_P$1") (pintype "passive"))
      (node (ref "Q11") (pin "D") (pinfunction "D_D") (pintype "passive"))
      (node (ref "Q11") (pin "D_PAD") (pinfunction "D_D_PAD") (pintype "passive"))
    )
    (net (code "61") (name "Net-(L1-2)") (class "Default")
      (node (ref "L1") (pin "P$2") (pinfunction "2_P$2") (pintype "passive"))
      (node (ref "L2") (pin "P$1") (pinfunction "1_P$1") (pintype "passive"))
      (node (ref "U2") (pin "1") (pinfunction "SWC_1") (pintype "input"))
      (node (ref "U2") (pin "6") (pinfunction "VCC_6") (pintype "power_in"))
      (node (ref "U2") (pin "7") (pinfunction "IPK_7") (pintype "bidirectional"))
      (node (ref "U2") (pin "8") (pinfunction "DC_8") (pintype "input"))
    )
    (net (code "62") (name "Net-(P1-P)") (class "Default")
      (node (ref "D2") (pin "A") (pinfunction "A_A") (pintype "passive"))
      (node (ref "D4") (pin "C") (pinfunction "C_C") (pintype "passive"))
      (node (ref "JP2") (pin "1") (pinfunction "1_1") (pintype "passive"))
      (node (ref "P1") (pin "1") (pinfunction "P_1") (pintype "passive"))
    )
    (net (code "63") (name "Net-(P2-P)") (class "Default")
      (node (ref "D3") (pin "A") (pinfunction "A_A") (pintype "passive"))
      (node (ref "D5") (pin "C") (pinfunction "C_C") (pintype "passive"))
      (node (ref "JP2") (pin "2") (pinfunction "2_2") (pintype "passive"))
      (node (ref "P2") (pin "1") (pinfunction "P_1") (pintype "passive"))
    )
    (net (code "64") (name "Net-(Q1-PadB)") (class "Default")
      (node (ref "Q1") (pin "B") (pinfunction "B_B") (pintype "passive"))
      (node (ref "R3") (pin "1") (pinfunction "1_1") (pintype "passive"))
    )
    (net (code "65") (name "Net-(Q1-PadC)") (class "Default")
      (node (ref "Q1") (pin "C") (pinfunction "C_C") (pintype "passive"))
      (node (ref "R1") (pin "1") (pinfunction "1_1") (pintype "passive"))
    )
    (net (code "66") (name "Net-(Q2-PadB)") (class "Default")
      (node (ref "Q2") (pin "B") (pinfunction "B_B") (pintype "passive"))
      (node (ref "R1") (pin "2") (pinfunction "2_2") (pintype "passive"))
      (node (ref "R2") (pin "1") (pinfunction "1_1") (pintype "passive"))
    )
    (net (code "67") (name "Net-(Q2-PadC)") (class "Default")
      (node (ref "Q2") (pin "C") (pinfunction "C_C") (pintype "passive"))
      (node (ref "R30") (pin "1") (pinfunction "1_1") (pintype "passive"))
    )
    (net (code "68") (name "Net-(Q3-PadB)") (class "Default")
      (node (ref "Q3") (pin "B") (pinfunction "B_B") (pintype "passive"))
      (node (ref "R7") (pin "1") (pinfunction "1_1") (pintype "passive"))
    )
    (net (code "69") (name "Net-(Q3-PadC)") (class "Default")
      (node (ref "Q3") (pin "C") (pinfunction "C_C") (pintype "passive"))
      (node (ref "R5") (pin "1") (pinfunction "1_1") (pintype "passive"))
    )
    (net (code "70") (name "Net-(Q4-PadB)") (class "Default")
      (node (ref "Q4") (pin "B") (pinfunction "B_B") (pintype "passive"))
      (node (ref "R5") (pin "2") (pinfunction "2_2") (pintype "passive"))
      (node (ref "R6") (pin "1") (pinfunction "1_1") (pintype "passive"))
    )
    (net (code "71") (name "Net-(Q4-PadC)") (class "Default")
      (node (ref "Q4") (pin "C") (pinfunction "C_C") (pintype "passive"))
      (node (ref "R31") (pin "1") (pinfunction "1_1") (pintype "passive"))
    )
    (net (code "72") (name "Net-(Q5-PadB)") (class "Default")
      (node (ref "Q5") (pin "B") (pinfunction "B_B") (pintype "passive"))
      (node (ref "R11") (pin "1") (pinfunction "1_1") (pintype "passive"))
    )
    (net (code "73") (name "Net-(Q5-PadC)") (class "Default")
      (node (ref "Q5") (pin "C") (pinfunction "C_C") (pintype "passive"))
      (node (ref "R9") (pin "1") (pinfunction "1_1") (pintype "passive"))
    )
    (net (code "74") (name "Net-(Q6-PadB)") (class "Default")
      (node (ref "Q6") (pin "B") (pinfunction "B_B") (pintype "passive"))
      (node (ref "R10") (pin "1") (pinfunction "1_1") (pintype "passive"))
      (node (ref "R9") (pin "2") (pinfunction "2_2") (pintype "passive"))
    )
    (net (code "75") (name "Net-(Q6-PadC)") (class "Default")
      (node (ref "Q6") (pin "C") (pinfunction "C_C") (pintype "passive"))
      (node (ref "R32") (pin "1") (pinfunction "1_1") (pintype "passive"))
    )
    (net (code "76") (name "Net-(Q7-PadB)") (class "Default")
      (node (ref "Q7") (pin "B") (pinfunction "B_B") (pintype "passive"))
      (node (ref "R15") (pin "1") (pinfunction "1_1") (pintype "passive"))
    )
    (net (code "77") (name "Net-(Q7-PadC)") (class "Default")
      (node (ref "Q7") (pin "C") (pinfunction "C_C") (pintype "passive"))
      (node (ref "R13") (pin "1") (pinfunction "1_1") (pintype "passive"))
    )
    (net (code "78") (name "Net-(Q8-PadB)") (class "Default")
      (node (ref "Q8") (pin "B") (pinfunction "B_B") (pintype "passive"))
      (node (ref "R13") (pin "2") (pinfunction "2_2") (pintype "passive"))
      (node (ref "R14") (pin "1") (pinfunction "1_1") (pintype "passive"))
    )
    (net (code "79") (name "Net-(Q8-PadC)") (class "Default")
      (node (ref "Q8") (pin "C") (pinfunction "C_C") (pintype "passive"))
      (node (ref "R33") (pin "1") (pinfunction "1_1") (pintype "passive"))
    )
    (net (code "80") (name "Net-(Q9-PadB)") (class "Default")
      (node (ref "Q9") (pin "B") (pinfunction "B_B") (pintype "passive"))
      (node (ref "R19") (pin "1") (pinfunction "1_1") (pintype "passive"))
    )
    (net (code "81") (name "Net-(Q10-PadB)") (class "Default")
      (node (ref "Q10") (pin "B") (pinfunction "B_B") (pintype "passive"))
      (node (ref "R17") (pin "1") (pinfunction "1_1") (pintype "passive"))
    )
    (net (code "82") (name "Net-(R21-Pad2)") (class "Default")
      (node (ref "R21") (pin "2") (pinfunction "2_2") (pintype "passive"))
      (node (ref "TM1") (pin "E") (pinfunction "E_E") (pintype "passive"))
    )
    (net (code "83") (name "Net-(R22-Pad1)") (class "Default")
      (node (ref "R22") (pin "1") (pinfunction "1_1") (pintype "passive"))
      (node (ref "TM1") (pin "A") (pinfunction "A_A") (pintype "passive"))
    )
    (net (code "84") (name "Net-(U1-AREF)") (class "Default")
      (node (ref "C13") (pin "1") (pinfunction "1_1") (pintype "passive"))
      (node (ref "U1") (pin "20") (pinfunction "AREF_20") (pintype "bidirectional"))
    )
    (net (code "85") (name "Net-(U1-PB6(XTAL1{slash}TOSC1))") (class "Default")
      (node (ref "C10") (pin "1") (pinfunction "1_1") (pintype "passive"))
      (node (ref "U1") (pin "7") (pinfunction "PB6(XTAL1/TOSC1)_7") (pintype "bidirectional"))
      (node (ref "Y1") (pin "3") (pinfunction "2_3") (pintype "passive"))
    )
    (net (code "86") (name "Net-(U1-PB7(XTAL2{slash}TOSC2))") (class "Default")
      (node (ref "C5") (pin "1") (pinfunction "1_1") (pintype "passive"))
      (node (ref "U1") (pin "8") (pinfunction "PB7(XTAL2/TOSC2)_8") (pintype "bidirectional"))
      (node (ref "Y1") (pin "1") (pinfunction "1_1") (pintype "passive"))
    )
    (net (code "87") (name "Net-(U1-PC0(ADC0))") (class "Default")
      (node (ref "R18") (pin "2") (pinfunction "2_2") (pintype "passive"))
      (node (ref "SW2") (pin "P2_SW") (pinfunction "P2_SW_P2_SW") (pintype "bidirectional"))
      (node (ref "U1") (pin "23") (pinfunction "PC0(ADC0)_23") (pintype "bidirectional"))
    )
    (net (code "88") (name "Net-(U1-PC1(ADC1))") (class "Default")
      (node (ref "R20") (pin "2") (pinfunction "2_2") (pintype "passive"))
      (node (ref "SW1") (pin "P2_SW") (pinfunction "P2_SW_P2_SW") (pintype "bidirectional"))
      (node (ref "U1") (pin "24") (pinfunction "PC1(ADC1)_24") (pintype "bidirectional"))
    )
    (net (code "89") (name "Net-(U1-PC6({slash}RESET))") (class "Default")
      (node (ref "C12") (pin "2") (pinfunction "2_2") (pintype "passive"))
      (node (ref "R26") (pin "2") (pinfunction "2_2") (pintype "passive"))
      (node (ref "U1") (pin "29") (pinfunction "PC6(/RESET)_29") (pintype "bidirectional"))
    )
    (net (code "90") (name "Net-(U2-COMP)") (class "Default")
      (node (ref "C9") (pin "1") (pinfunction "1_1") (pintype "passive"))
      (node (ref "TM1") (pin "S") (pinfunction "S_S") (pintype "passive"))
      (node (ref "U2") (pin "5") (pinfunction "COMP_5") (pintype "input"))
    )
    (net (code "91") (name "Net-(U2-SWE)") (class "Default")
      (node (ref "Q11") (pin "G") (pinfunction "G_G") (pintype "passive"))
      (node (ref "R23") (pin "1") (pinfunction "1_1") (pintype "passive"))
      (node (ref "U2") (pin "2") (pinfunction "SWE_2") (pintype "input"))
    )
    (net (code "92") (name "Net-(U2-TC)") (class "Default")
      (node (ref "C1") (pin "1") (pinfunction "1_1") (pintype "passive"))
      (node (ref "U2") (pin "3") (pinfunction "TC_3") (pintype "input"))
    )
    (net (code "93") (name "Net-(U4-P1_OSCI)") (class "Default")
      (node (ref "U4") (pin "1") (pinfunction "P1_OSCI_1") (pintype "bidirectional"))
      (node (ref "X1") (pin "4") (pinfunction "2_4") (pintype "passive"))
    )
    (net (code "94") (name "Net-(U4-P2_OSCO)") (class "Default")
      (node (ref "U4") (pin "2") (pinfunction "P2_OSCO_2") (pintype "bidirectional"))
      (node (ref "X1") (pin "1") (pinfunction "1_1") (pintype "passive"))
    )
    (net (code "95") (name "unconnected-(U1-ADC6-Pad19)") (class "Default")
      (node (ref "U1") (pin "19") (pinfunction "ADC6_19") (pintype "bidirectional"))
    )
    (net (code "96") (name "unconnected-(U1-ADC7-Pad22)") (class "Default")
      (node (ref "U1") (pin "22") (pinfunction "ADC7_22") (pintype "bidirectional"))
    )
    (net (code "97") (name "unconnected-(U1-PB0(ICP)-Pad12)") (class "Default")
      (node (ref "U1") (pin "12") (pinfunction "PB0(ICP)_12") (pintype "bidirectional"))
    )
    (net (code "98") (name "unconnected-(U1-PB1(OC1A)-Pad13)") (class "Default")
      (node (ref "U1") (pin "13") (pinfunction "PB1(OC1A)_13") (pintype "bidirectional"))
    )
    (net (code "99") (name "unconnected-(U1-PC2(ADC2)-Pad25)") (class "Default")
      (node (ref "U1") (pin "25") (pinfunction "PC2(ADC2)_25") (pintype "bidirectional"))
    )
    (net (code "100") (name "unconnected-(U1-PC3(ADC3)-Pad26)") (class "Default")
      (node (ref "U1") (pin "26") (pinfunction "PC3(ADC3)_26") (pintype "bidirectional"))
    )
    (net (code "101") (name "unconnected-(U4-P7_INT_N_CLKOUT-Pad7)") (class "Default")
      (node (ref "U4") (pin "7") (pinfunction "P7_INT_N_CLKOUT_7") (pintype "output"))
    )
  )
)
